# SensorStick_IMUedits_HeaderPins.net
KiCad netlist of a schematic drawn in EAGLE
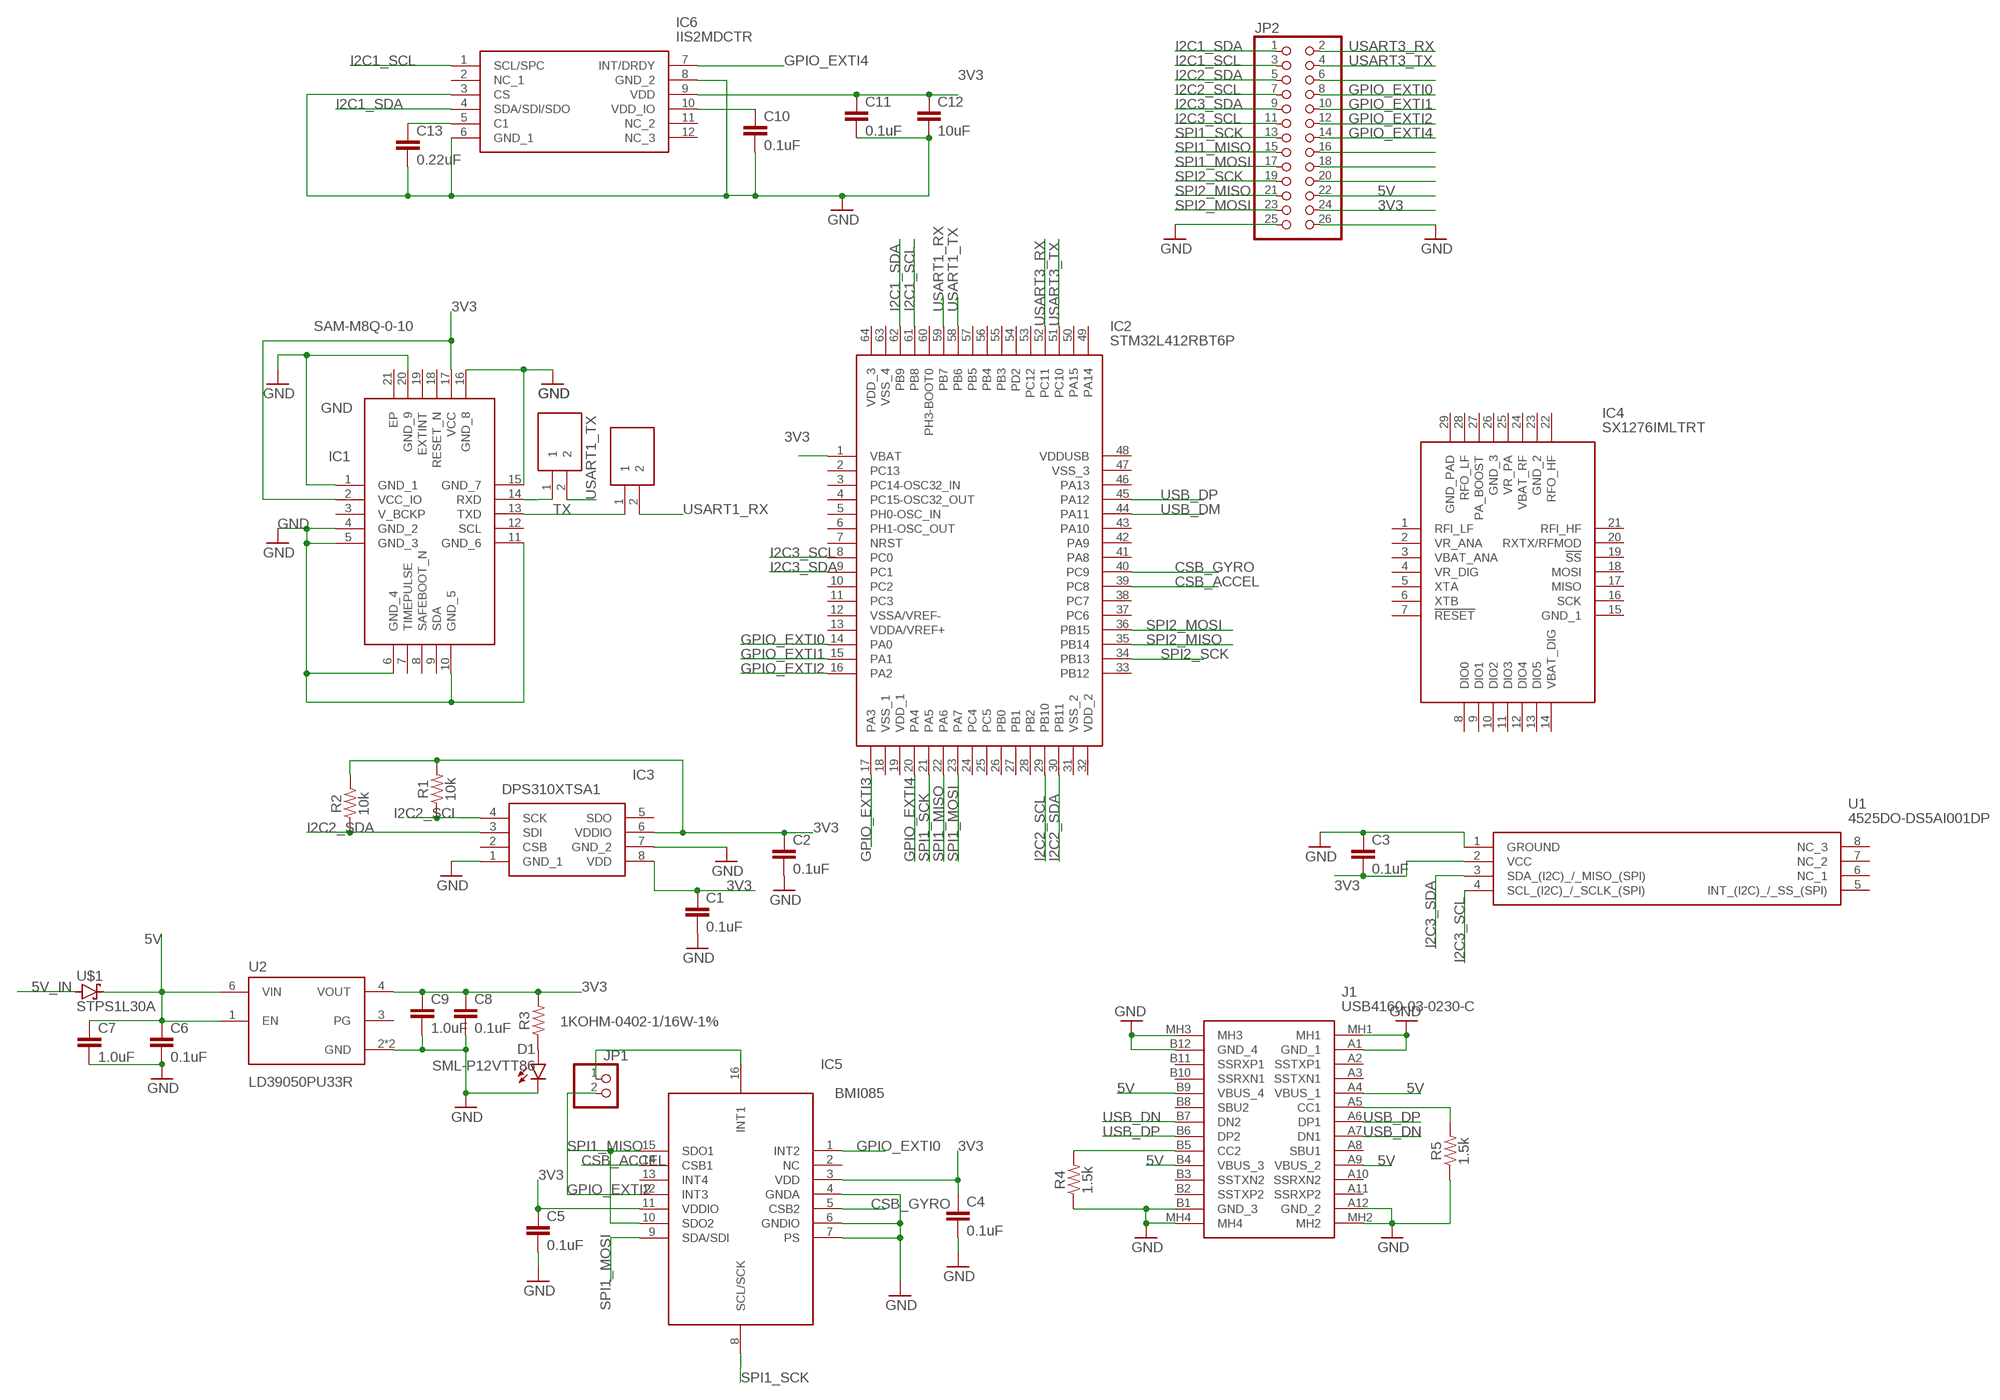
[diagram p0: schematic, sheet 1]

(export (version "E")
  (design (tool "Eeschema 10.0.6"))
  (components
    (comp (ref "C1")
      (value "0.1uF")
      (footprint "eagle-import:0402")
      (libsource (lib "eagle-import") (part "0.1UF-0402-6.3V-10%-X7R"))
    )
    (comp (ref "C2")
      (value "0.1uF")
      (footprint "eagle-import:0402")
      (libsource (lib "eagle-import") (part "0.1UF-0402-6.3V-10%-X7R"))
    )
    (comp (ref "C3")
      (value "0.1uF")
      (footprint "eagle-import:0402")
      (libsource (lib "eagle-import") (part "0.1UF-0402-6.3V-10%-X7R"))
    )
    (comp (ref "C4")
      (value "0.1uF")
      (footprint "eagle-import:0402")
      (libsource (lib "eagle-import") (part "0.1UF-0402-6.3V-10%-X7R"))
    )
    (comp (ref "C5")
      (value "0.1uF")
      (footprint "eagle-import:0402")
      (libsource (lib "eagle-import") (part "0.1UF-0402-6.3V-10%-X7R"))
    )
    (comp (ref "C6")
      (value "0.1uF")
      (footprint "eagle-import:0402")
      (libsource (lib "eagle-import") (part "0.1UF-0402-6.3V-10%-X7R"))
    )
    (comp (ref "C7")
      (value "1.0uF")
      (footprint "eagle-import:0402")
      (libsource (lib "eagle-import") (part "1.0UF-0402-16V-10%"))
    )
    (comp (ref "C8")
      (value "0.1uF")
      (footprint "eagle-import:0402")
      (libsource (lib "eagle-import") (part "0.1UF-0402-6.3V-10%-X7R"))
    )
    (comp (ref "C9")
      (value "1.0uF")
      (footprint "eagle-import:0402")
      (libsource (lib "eagle-import") (part "1.0UF-0402-16V-10%"))
    )
    (comp (ref "C10")
      (value "0.1uF")
      (footprint "eagle-import:0402")
      (libsource (lib "eagle-import") (part "0.1UF-0402-6.3V-10%-X7R"))
    )
    (comp (ref "C11")
      (value "0.1uF")
      (footprint "eagle-import:0402")
      (libsource (lib "eagle-import") (part "0.1UF-0402-6.3V-10%-X7R"))
    )
    (comp (ref "C12")
      (value "10uF")
      (footprint "eagle-import:0603")
      (libsource (lib "eagle-import") (part "10UF-0603-6.3V-20%"))
    )
    (comp (ref "C13")
      (value "0.22uF")
      (footprint "eagle-import:0603")
      (libsource (lib "eagle-import") (part "0.22UF-0603-25V-10%"))
    )
    (comp (ref "D1")
      (value "SML-P12VTT86")
      (footprint "eagle-import:LED_SML-P11UTT86R")
      (fields (field (name "MF") "Rohm"))
      (libsource (lib "eagle-import") (part "SML-P12VTT86"))
    )
    (comp (ref "FB1")
      (value "BLM15HD102SN1")
      (footprint "eagle-import:NFZ15SG152SN10B")
      (libsource (lib "eagle-import") (part "BLM15HD102SN1"))
    )
    (comp (ref "FB2")
      (value "BLM15HD102SN1")
      (footprint "eagle-import:NFZ15SG152SN10B")
      (libsource (lib "eagle-import") (part "BLM15HD102SN1"))
    )
    (comp (ref "IC1")
      (value "SAM-M8Q-0-10")
      (footprint "eagle-import:SAMM8Q010")
      (libsource (lib "eagle-import") (part "SAM-M8Q-0-10"))
    )
    (comp (ref "IC2")
      (value "STM32L412RBT6P")
      (footprint "eagle-import:QFP50P1200X1200X160-64N")
      (fields (field (name "MOUSER_PART_NUMBER") "511-STM32L412RBT6P"))
      (libsource (lib "eagle-import") (part "STM32L412RBT6P"))
    )
    (comp (ref "IC3")
      (value "DPS310XTSA1")
      (footprint "eagle-import:DPS310XTSA1")
      (fields (field (name "MOUSER_PART_NUMBER") "726-DPS310XTSA1"))
      (libsource (lib "eagle-import") (part "DPS310XTSA1"))
    )
    (comp (ref "IC4")
      (value "SX1276IMLTRT")
      (footprint "eagle-import:QFN65P600X600X100-29N")
      (fields (field (name "MOUSER_PART_NUMBER") "947-SX1276IMLTRT"))
      (libsource (lib "eagle-import") (part "SX1276IMLTRT"))
    )
    (comp (ref "IC5")
      (value "BMI085")
      (footprint "eagle-import:BMI085")
      (fields (field (name "MOUSER_PART_NUMBER") "262-BMI085"))
      (libsource (lib "eagle-import") (part "BMI085"))
    )
    (comp (ref "IC6")
      (value "IIS2MDCTR")
      (footprint "eagle-import:IIS2MDCTR")
      (fields (field (name "MOUSER_PART_NUMBER") "511-IIS2MDCTR"))
      (libsource (lib "eagle-import") (part "IIS2MDCTR"))
    )
    (comp (ref "J1")
      (value "USB4160-03-0230-C")
      (footprint "eagle-import:USB4160030230C")
      (fields (field (name "MOUSER_PART_NUMBER") "640-USB4160-3-0230-C"))
      (libsource (lib "eagle-import") (part "USB4160-03-0230-C"))
    )
    (comp (ref "JP1")
      (value "PINHD-1X2")
      (footprint "eagle-import:1X02")
      (libsource (lib "eagle-import") (part "PINHD-1X2"))
    )
    (comp (ref "JP2")
      (value "PINHD-2X13")
      (footprint "eagle-import:2X13")
      (libsource (lib "eagle-import") (part "PINHD-2X13"))
    )
    (comp (ref "R1")
      (value "10k")
      (footprint "eagle-import:0402")
      (libsource (lib "eagle-import") (part "10KOHM-0402-1/16W-1%"))
    )
    (comp (ref "R2")
      (value "10k")
      (footprint "eagle-import:0402")
      (libsource (lib "eagle-import") (part "10KOHM-0402-1/16W-1%"))
    )
    (comp (ref "R3")
      (value "1KOHM-0402-1/16W-1%")
      (footprint "eagle-import:0402")
      (libsource (lib "eagle-import") (part "1KOHM-0402-1/16W-1%"))
    )
    (comp (ref "R4")
      (value "1.5k")
      (footprint "eagle-import:0603")
      (libsource (lib "eagle-import") (part "1.5KOHM-0603-1/10W-1%"))
    )
    (comp (ref "R5")
      (value "1.5k")
      (footprint "eagle-import:0603")
      (libsource (lib "eagle-import") (part "1.5KOHM-0603-1/10W-1%"))
    )
    (comp (ref "U$1")
      (value "STPS1L30A")
      (footprint "eagle-import:DIOM5226X223N")
      (libsource (lib "eagle-import") (part "STPS1L30A"))
    )
    (comp (ref "U1")
      (value "4525DO-DS5AI001DP")
      (footprint "eagle-import:4525DO-DS...P")
      (fields (field (name "MOUSER_PART_NUMBER") "824-4525DODS5AI001DP"))
      (libsource (lib "eagle-import") (part "4525DO-DS5AI001DP"))
    )
    (comp (ref "U2")
      (value "LD39050PU33R")
      (footprint "eagle-import:SON95P300X300X100-7N")
      (fields (field (name "MF") "STMicroelectronics"))
      (libsource (lib "eagle-import") (part "LD39050PU33R"))
    )
  )
  (nets
    (net (code "1") (name "/3V3") (class "Default")
      (node (ref "C1") (pin "1") (pinfunction "1_1") (pintype "passive"))
      (node (ref "C11") (pin "1") (pinfunction "1_1") (pintype "passive"))
      (node (ref "C12") (pin "1") (pinfunction "1_1") (pintype "passive"))
      (node (ref "C2") (pin "1") (pinfunction "1_1") (pintype "passive"))
      (node (ref "C3") (pin "2") (pinfunction "2_2") (pintype "passive"))
      (node (ref "C4") (pin "1") (pinfunction "1_1") (pintype "passive"))
      (node (ref "C5") (pin "1") (pinfunction "1_1") (pintype "passive"))
      (node (ref "C8") (pin "1") (pinfunction "1_1") (pintype "passive"))
      (node (ref "C9") (pin "1") (pinfunction "1_1") (pintype "passive"))
      (node (ref "IC1") (pin "17") (pinfunction "VCC_17") (pintype "bidirectional"))
      (node (ref "IC1") (pin "2") (pinfunction "VCC_IO_2") (pintype "bidirectional"))
      (node (ref "IC2") (pin "1") (pinfunction "VBAT_1") (pintype "bidirectional"))
      (node (ref "IC3") (pin "6") (pinfunction "VDDIO_6") (pintype "bidirectional"))
      (node (ref "IC3") (pin "8") (pinfunction "VDD_8") (pintype "bidirectional"))
      (node (ref "IC5") (pin "11") (pinfunction "VDDIO_11") (pintype "bidirectional"))
      (node (ref "IC5") (pin "3") (pinfunction "VDD_3") (pintype "bidirectional"))
      (node (ref "IC6") (pin "9") (pinfunction "VDD_9") (pintype "bidirectional"))
      (node (ref "JP2") (pin "24") (pinfunction "24_24") (pintype "passive"))
      (node (ref "R1") (pin "2") (pinfunction "2_2") (pintype "passive"))
      (node (ref "R2") (pin "2") (pinfunction "2_2") (pintype "passive"))
      (node (ref "R3") (pin "2") (pinfunction "2_2") (pintype "passive"))
      (node (ref "U1") (pin "2") (pinfunction "VCC_2") (pintype "power_in"))
      (node (ref "U2") (pin "4") (pinfunction "VOUT_4") (pintype "output"))
    )
    (net (code "2") (name "/5V") (class "Default")
      (node (ref "C6") (pin "1") (pinfunction "1_1") (pintype "passive"))
      (node (ref "C7") (pin "1") (pinfunction "1_1") (pintype "passive"))
      (node (ref "J1") (pin "A4") (pinfunction "VBUS_1_A4") (pintype "bidirectional"))
      (node (ref "J1") (pin "A9") (pinfunction "VBUS_2_A9") (pintype "bidirectional"))
      (node (ref "J1") (pin "B4") (pinfunction "VBUS_3_B4") (pintype "bidirectional"))
      (node (ref "J1") (pin "B9") (pinfunction "VBUS_4_B9") (pintype "bidirectional"))
      (node (ref "JP2") (pin "22") (pinfunction "22_22") (pintype "passive"))
      (node (ref "U$1") (pin "1") (pinfunction "C_1") (pintype "passive"))
      (node (ref "U2") (pin "1") (pinfunction "EN_1") (pintype "input"))
      (node (ref "U2") (pin "6") (pinfunction "VIN_6") (pintype "power_in"))
    )
    (net (code "3") (name "/5V_IN") (class "Default")
      (node (ref "U$1") (pin "2") (pinfunction "A_2") (pintype "passive"))
    )
    (net (code "4") (name "/CSB_ACCEL") (class "Default")
      (node (ref "IC2") (pin "39") (pinfunction "PC8_39") (pintype "bidirectional"))
      (node (ref "IC5") (pin "14") (pinfunction "CSB1_14") (pintype "bidirectional"))
    )
    (net (code "5") (name "/CSB_GYRO") (class "Default")
      (node (ref "IC2") (pin "40") (pinfunction "PC9_40") (pintype "bidirectional"))
      (node (ref "IC5") (pin "5") (pinfunction "CSB2_5") (pintype "bidirectional"))
    )
    (net (code "6") (name "/GPIO_EXTI0") (class "Default")
      (node (ref "IC2") (pin "14") (pinfunction "PA0_14") (pintype "bidirectional"))
      (node (ref "IC5") (pin "1") (pinfunction "INT2_1") (pintype "bidirectional"))
      (node (ref "JP2") (pin "8") (pinfunction "8_8") (pintype "passive"))
    )
    (net (code "7") (name "/GPIO_EXTI1") (class "Default")
      (node (ref "IC2") (pin "15") (pinfunction "PA1_15") (pintype "bidirectional"))
      (node (ref "JP2") (pin "10") (pinfunction "10_10") (pintype "passive"))
    )
    (net (code "8") (name "/GPIO_EXTI2") (class "Default")
      (node (ref "IC2") (pin "16") (pinfunction "PA2_16") (pintype "bidirectional"))
      (node (ref "IC5") (pin "12") (pinfunction "INT3_12") (pintype "bidirectional"))
      (node (ref "JP1") (pin "2") (pinfunction "2_2") (pintype "passive"))
      (node (ref "JP2") (pin "12") (pinfunction "12_12") (pintype "passive"))
    )
    (net (code "9") (name "/GPIO_EXTI3") (class "Default")
      (node (ref "IC2") (pin "17") (pinfunction "PA3_17") (pintype "bidirectional"))
    )
    (net (code "10") (name "/GPIO_EXTI4") (class "Default")
      (node (ref "IC2") (pin "20") (pinfunction "PA4_20") (pintype "bidirectional"))
      (node (ref "IC6") (pin "7") (pinfunction "INT/DRDY_7") (pintype "bidirectional"))
      (node (ref "JP2") (pin "14") (pinfunction "14_14") (pintype "passive"))
    )
    (net (code "11") (name "/I2C1_SCL") (class "Default")
      (node (ref "IC2") (pin "61") (pinfunction "PB8_61") (pintype "bidirectional"))
      (node (ref "IC6") (pin "1") (pinfunction "SCL/SPC_1") (pintype "bidirectional"))
      (node (ref "JP2") (pin "3") (pinfunction "3_3") (pintype "passive"))
    )
    (net (code "12") (name "/I2C1_SDA") (class "Default")
      (node (ref "IC2") (pin "62") (pinfunction "PB9_62") (pintype "bidirectional"))
      (node (ref "IC6") (pin "4") (pinfunction "SDA/SDI/SDO_4") (pintype "bidirectional"))
      (node (ref "JP2") (pin "1") (pinfunction "1_1") (pintype "passive"))
    )
    (net (code "13") (name "/I2C2_SCL") (class "Default")
      (node (ref "IC2") (pin "29") (pinfunction "PB10_29") (pintype "bidirectional"))
      (node (ref "IC3") (pin "4") (pinfunction "SCK_4") (pintype "bidirectional"))
      (node (ref "JP2") (pin "7") (pinfunction "7_7") (pintype "passive"))
      (node (ref "R1") (pin "1") (pinfunction "1_1") (pintype "passive"))
    )
    (net (code "14") (name "/I2C2_SDA") (class "Default")
      (node (ref "IC2") (pin "30") (pinfunction "PB11_30") (pintype "bidirectional"))
      (node (ref "IC3") (pin "3") (pinfunction "SDI_3") (pintype "bidirectional"))
      (node (ref "JP2") (pin "5") (pinfunction "5_5") (pintype "passive"))
      (node (ref "R2") (pin "1") (pinfunction "1_1") (pintype "passive"))
    )
    (net (code "15") (name "/I2C3_SCL") (class "Default")
      (node (ref "IC2") (pin "8") (pinfunction "PC0_8") (pintype "bidirectional"))
      (node (ref "JP2") (pin "11") (pinfunction "11_11") (pintype "passive"))
      (node (ref "U1") (pin "4") (pinfunction "SCL_(I2C)_/_SCLK_(SPI)_4") (pintype "bidirectional"))
    )
    (net (code "16") (name "/I2C3_SDA") (class "Default")
      (node (ref "IC2") (pin "9") (pinfunction "PC1_9") (pintype "bidirectional"))
      (node (ref "JP2") (pin "9") (pinfunction "9_9") (pintype "passive"))
      (node (ref "U1") (pin "3") (pinfunction "SDA_(I2C)_/_MISO_(SPI)_3") (pintype "bidirectional"))
    )
    (net (code "17") (name "/SPI1_MISO") (class "Default")
      (node (ref "IC2") (pin "22") (pinfunction "PA6_22") (pintype "bidirectional"))
      (node (ref "IC5") (pin "10") (pinfunction "SDO2_10") (pintype "bidirectional"))
      (node (ref "IC5") (pin "15") (pinfunction "SDO1_15") (pintype "bidirectional"))
      (node (ref "JP2") (pin "15") (pinfunction "15_15") (pintype "passive"))
    )
    (net (code "18") (name "/SPI1_MOSI") (class "Default")
      (node (ref "IC2") (pin "23") (pinfunction "PA7_23") (pintype "bidirectional"))
      (node (ref "IC5") (pin "9") (pinfunction "SDA/SDI_9") (pintype "bidirectional"))
      (node (ref "JP2") (pin "17") (pinfunction "17_17") (pintype "passive"))
    )
    (net (code "19") (name "/SPI1_SCK") (class "Default")
      (node (ref "IC2") (pin "21") (pinfunction "PA5_21") (pintype "bidirectional"))
      (node (ref "IC5") (pin "8") (pinfunction "SCL/SCK_8") (pintype "bidirectional"))
      (node (ref "JP2") (pin "13") (pinfunction "13_13") (pintype "passive"))
    )
    (net (code "20") (name "/SPI2_MISO") (class "Default")
      (node (ref "IC2") (pin "35") (pinfunction "PB14_35") (pintype "bidirectional"))
      (node (ref "JP2") (pin "21") (pinfunction "21_21") (pintype "passive"))
    )
    (net (code "21") (name "/SPI2_MOSI") (class "Default")
      (node (ref "IC2") (pin "36") (pinfunction "PB15_36") (pintype "bidirectional"))
      (node (ref "JP2") (pin "23") (pinfunction "23_23") (pintype "passive"))
    )
    (net (code "22") (name "/SPI2_SCK") (class "Default")
      (node (ref "IC2") (pin "34") (pinfunction "PB13_34") (pintype "bidirectional"))
      (node (ref "JP2") (pin "19") (pinfunction "19_19") (pintype "passive"))
    )
    (net (code "23") (name "/TX") (class "Default")
      (node (ref "FB1") (pin "1") (pinfunction "1_1") (pintype "bidirectional"))
      (node (ref "IC1") (pin "13") (pinfunction "TXD_13") (pintype "bidirectional"))
    )
    (net (code "24") (name "/USART1_RX") (class "Default")
      (node (ref "FB1") (pin "2") (pinfunction "2_2") (pintype "bidirectional"))
      (node (ref "IC2") (pin "59") (pinfunction "PB7_59") (pintype "bidirectional"))
    )
    (net (code "25") (name "/USART1_TX") (class "Default")
      (node (ref "FB2") (pin "2") (pinfunction "2_2") (pintype "bidirectional"))
      (node (ref "IC2") (pin "58") (pinfunction "PB6_58") (pintype "bidirectional"))
    )
    (net (code "26") (name "/USART3_RX") (class "Default")
      (node (ref "IC2") (pin "52") (pinfunction "PC11_52") (pintype "bidirectional"))
      (node (ref "JP2") (pin "2") (pinfunction "2_2") (pintype "passive"))
    )
    (net (code "27") (name "/USART3_TX") (class "Default")
      (node (ref "IC2") (pin "51") (pinfunction "PC10_51") (pintype "bidirectional"))
      (node (ref "JP2") (pin "4") (pinfunction "4_4") (pintype "passive"))
    )
    (net (code "28") (name "/USB_DM") (class "Default")
      (node (ref "IC2") (pin "44") (pinfunction "PA11_44") (pintype "bidirectional"))
    )
    (net (code "29") (name "/USB_DN") (class "Default")
      (node (ref "J1") (pin "A7") (pinfunction "DN1_A7") (pintype "bidirectional"))
      (node (ref "J1") (pin "B7") (pinfunction "DN2_B7") (pintype "bidirectional"))
    )
    (net (code "30") (name "/USB_DP") (class "Default")
      (node (ref "IC2") (pin "45") (pinfunction "PA12_45") (pintype "bidirectional"))
      (node (ref "J1") (pin "A6") (pinfunction "DP1_A6") (pintype "bidirectional"))
      (node (ref "J1") (pin "B6") (pinfunction "DP2_B6") (pintype "bidirectional"))
    )
    (net (code "31") (name "GND") (class "Default")
      (node (ref "C1") (pin "2") (pinfunction "2_2") (pintype "passive"))
      (node (ref "C10") (pin "2") (pinfunction "2_2") (pintype "passive"))
      (node (ref "C11") (pin "2") (pinfunction "2_2") (pintype "passive"))
      (node (ref "C12") (pin "2") (pinfunction "2_2") (pintype "passive"))
      (node (ref "C13") (pin "2") (pinfunction "2_2") (pintype "passive"))
      (node (ref "C2") (pin "2") (pinfunction "2_2") (pintype "passive"))
      (node (ref "C3") (pin "1") (pinfunction "1_1") (pintype "passive"))
      (node (ref "C4") (pin "2") (pinfunction "2_2") (pintype "passive"))
      (node (ref "C5") (pin "2") (pinfunction "2_2") (pintype "passive"))
      (node (ref "C6") (pin "2") (pinfunction "2_2") (pintype "passive"))
      (node (ref "C7") (pin "2") (pinfunction "2_2") (pintype "passive"))
      (node (ref "C8") (pin "2") (pinfunction "2_2") (pintype "passive"))
      (node (ref "C9") (pin "2") (pinfunction "2_2") (pintype "passive"))
      (node (ref "D1") (pin "C") (pinfunction "C_C") (pintype "passive"))
      (node (ref "IC1") (pin "1") (pinfunction "GND_1_1") (pintype "bidirectional"))
      (node (ref "IC1") (pin "10") (pinfunction "GND_5_10") (pintype "bidirectional"))
      (node (ref "IC1") (pin "11") (pinfunction "GND_6_11") (pintype "bidirectional"))
      (node (ref "IC1") (pin "15") (pinfunction "GND_7_15") (pintype "bidirectional"))
      (node (ref "IC1") (pin "16") (pinfunction "GND_8_16") (pintype "bidirectional"))
      (node (ref "IC1") (pin "20") (pinfunction "GND_9_20") (pintype "bidirectional"))
      (node (ref "IC1") (pin "4") (pinfunction "GND_2_4") (pintype "bidirectional"))
      (node (ref "IC1") (pin "5") (pinfunction "GND_3_5") (pintype "bidirectional"))
      (node (ref "IC1") (pin "6") (pinfunction "GND_4_6") (pintype "bidirectional"))
      (node (ref "IC3") (pin "1") (pinfunction "GND_1_1") (pintype "bidirectional"))
      (node (ref "IC3") (pin "7") (pinfunction "GND_2_7") (pintype "bidirectional"))
      (node (ref "IC5") (pin "4") (pinfunction "GNDA_4") (pintype "bidirectional"))
      (node (ref "IC5") (pin "6") (pinfunction "GNDIO_6") (pintype "bidirectional"))
      (node (ref "IC5") (pin "7") (pinfunction "PS_7") (pintype "bidirectional"))
      (node (ref "IC6") (pin "3") (pinfunction "CS_3") (pintype "bidirectional"))
      (node (ref "IC6") (pin "6") (pinfunction "GND_1_6") (pintype "bidirectional"))
      (node (ref "IC6") (pin "8") (pinfunction "GND_2_8") (pintype "bidirectional"))
      (node (ref "J1") (pin "A1") (pinfunction "GND_1_A1") (pintype "bidirectional"))
      (node (ref "J1") (pin "A12") (pinfunction "GND_2_A12") (pintype "bidirectional"))
      (node (ref "J1") (pin "B1") (pinfunction "GND_3_B1") (pintype "bidirectional"))
      (node (ref "J1") (pin "B12") (pinfunction "GND_4_B12") (pintype "bidirectional"))
      (node (ref "J1") (pin "MH1") (pinfunction "MH1_MH1") (pintype "bidirectional"))
      (node (ref "J1") (pin "MH2") (pinfunction "MH2_MH2") (pintype "bidirectional"))
      (node (ref "J1") (pin "MH3") (pinfunction "MH3_MH3") (pintype "bidirectional"))
      (node (ref "J1") (pin "MH4") (pinfunction "MH4_MH4") (pintype "bidirectional"))
      (node (ref "JP2") (pin "25") (pinfunction "25_25") (pintype "passive"))
      (node (ref "JP2") (pin "26") (pinfunction "26_26") (pintype "passive"))
      (node (ref "R4") (pin "1") (pinfunction "1_1") (pintype "passive"))
      (node (ref "R5") (pin "1") (pinfunction "1_1") (pintype "passive"))
      (node (ref "U1") (pin "1") (pinfunction "GROUND_1") (pintype "power_in"))
      (node (ref "U2") (pin "2") (pinfunction "GND_2") (pintype "power_in"))
      (node (ref "U2") (pin "7") (pinfunction "GND_7") (pintype "power_in"))
    )
    (net (code "32") (name "Net-(D1-PadA)") (class "Default")
      (node (ref "D1") (pin "A") (pinfunction "A_A") (pintype "passive"))
      (node (ref "R3") (pin "1") (pinfunction "1_1") (pintype "passive"))
    )
    (net (code "33") (name "Net-(IC1-RXD)") (class "Default")
      (node (ref "FB2") (pin "1") (pinfunction "1_1") (pintype "bidirectional"))
      (node (ref "IC1") (pin "14") (pinfunction "RXD_14") (pintype "bidirectional"))
    )
    (net (code "34") (name "Net-(IC5-INT1)") (class "Default")
      (node (ref "IC5") (pin "16") (pinfunction "INT1_16") (pintype "bidirectional"))
      (node (ref "JP1") (pin "1") (pinfunction "1_1") (pintype "passive"))
    )
    (net (code "35") (name "Net-(IC6-C1)") (class "Default")
      (node (ref "C13") (pin "1") (pinfunction "1_1") (pintype "passive"))
      (node (ref "IC6") (pin "5") (pinfunction "C1_5") (pintype "bidirectional"))
    )
    (net (code "36") (name "Net-(IC6-VDD_IO)") (class "Default")
      (node (ref "C10") (pin "1") (pinfunction "1_1") (pintype "passive"))
      (node (ref "IC6") (pin "10") (pinfunction "VDD_IO_10") (pintype "bidirectional"))
    )
    (net (code "37") (name "Net-(J1-CC1)") (class "Default")
      (node (ref "J1") (pin "A5") (pinfunction "CC1_A5") (pintype "bidirectional"))
      (node (ref "R5") (pin "2") (pinfunction "2_2") (pintype "passive"))
    )
    (net (code "38") (name "Net-(J1-CC2)") (class "Default")
      (node (ref "J1") (pin "B5") (pinfunction "CC2_B5") (pintype "bidirectional"))
      (node (ref "R4") (pin "2") (pinfunction "2_2") (pintype "passive"))
    )
    (net (code "39") (name "unconnected-(IC1-EP-Pad21)") (class "Default")
      (node (ref "IC1") (pin "21") (pinfunction "EP_21") (pintype "bidirectional"))
    )
    (net (code "40") (name "unconnected-(IC1-EXTINT-Pad19)") (class "Default")
      (node (ref "IC1") (pin "19") (pinfunction "EXTINT_19") (pintype "bidirectional"))
    )
    (net (code "41") (name "unconnected-(IC1-RESET_N-Pad18)") (class "Default")
      (node (ref "IC1") (pin "18") (pinfunction "RESET_N_18") (pintype "bidirectional"))
    )
    (net (code "42") (name "unconnected-(IC1-SAFEBOOT_N-Pad8)") (class "Default")
      (node (ref "IC1") (pin "8") (pinfunction "SAFEBOOT_N_8") (pintype "bidirectional"))
    )
    (net (code "43") (name "unconnected-(IC1-SCL-Pad12)") (class "Default")
      (node (ref "IC1") (pin "12") (pinfunction "SCL_12") (pintype "bidirectional"))
    )
    (net (code "44") (name "unconnected-(IC1-SDA-Pad9)") (class "Default")
      (node (ref "IC1") (pin "9") (pinfunction "SDA_9") (pintype "bidirectional"))
    )
    (net (code "45") (name "unconnected-(IC1-TIMEPULSE-Pad7)") (class "Default")
      (node (ref "IC1") (pin "7") (pinfunction "TIMEPULSE_7") (pintype "bidirectional"))
    )
    (net (code "46") (name "unconnected-(IC1-V_BCKP-Pad3)") (class "Default")
      (node (ref "IC1") (pin "3") (pinfunction "V_BCKP_3") (pintype "bidirectional"))
    )
    (net (code "47") (name "unconnected-(IC2-NRST-Pad7)") (class "Default")
      (node (ref "IC2") (pin "7") (pinfunction "NRST_7") (pintype "bidirectional"))
    )
    (net (code "48") (name "unconnected-(IC2-PA8-Pad41)") (class "Default")
      (node (ref "IC2") (pin "41") (pinfunction "PA8_41") (pintype "bidirectional"))
    )
    (net (code "49") (name "unconnected-(IC2-PA9-Pad42)") (class "Default")
      (node (ref "IC2") (pin "42") (pinfunction "PA9_42") (pintype "bidirectional"))
    )
    (net (code "50") (name "unconnected-(IC2-PA10-Pad43)") (class "Default")
      (node (ref "IC2") (pin "43") (pinfunction "PA10_43") (pintype "bidirectional"))
    )
    (net (code "51") (name "unconnected-(IC2-PA13-Pad46)") (class "Default")
      (node (ref "IC2") (pin "46") (pinfunction "PA13_46") (pintype "bidirectional"))
    )
    (net (code "52") (name "unconnected-(IC2-PA14-Pad49)") (class "Default")
      (node (ref "IC2") (pin "49") (pinfunction "PA14_49") (pintype "bidirectional"))
    )
    (net (code "53") (name "unconnected-(IC2-PA15-Pad50)") (class "Default")
      (node (ref "IC2") (pin "50") (pinfunction "PA15_50") (pintype "bidirectional"))
    )
    (net (code "54") (name "unconnected-(IC2-PB0-Pad26)") (class "Default")
      (node (ref "IC2") (pin "26") (pinfunction "PB0_26") (pintype "bidirectional"))
    )
    (net (code "55") (name "unconnected-(IC2-PB1-Pad27)") (class "Default")
      (node (ref "IC2") (pin "27") (pinfunction "PB1_27") (pintype "bidirectional"))
    )
    (net (code "56") (name "unconnected-(IC2-PB2-Pad28)") (class "Default")
      (node (ref "IC2") (pin "28") (pinfunction "PB2_28") (pintype "bidirectional"))
    )
    (net (code "57") (name "unconnected-(IC2-PB3-Pad55)") (class "Default")
      (node (ref "IC2") (pin "55") (pinfunction "PB3_55") (pintype "bidirectional"))
    )
    (net (code "58") (name "unconnected-(IC2-PB4-Pad56)") (class "Default")
      (node (ref "IC2") (pin "56") (pinfunction "PB4_56") (pintype "bidirectional"))
    )
    (net (code "59") (name "unconnected-(IC2-PB5-Pad57)") (class "Default")
      (node (ref "IC2") (pin "57") (pinfunction "PB5_57") (pintype "bidirectional"))
    )
    (net (code "60") (name "unconnected-(IC2-PB12-Pad33)") (class "Default")
      (node (ref "IC2") (pin "33") (pinfunction "PB12_33") (pintype "bidirectional"))
    )
    (net (code "61") (name "unconnected-(IC2-PC2-Pad10)") (class "Default")
      (node (ref "IC2") (pin "10") (pinfunction "PC2_10") (pintype "bidirectional"))
    )
    (net (code "62") (name "unconnected-(IC2-PC3-Pad11)") (class "Default")
      (node (ref "IC2") (pin "11") (pinfunction "PC3_11") (pintype "bidirectional"))
    )
    (net (code "63") (name "unconnected-(IC2-PC4-Pad24)") (class "Default")
      (node (ref "IC2") (pin "24") (pinfunction "PC4_24") (pintype "bidirectional"))
    )
    (net (code "64") (name "unconnected-(IC2-PC5-Pad25)") (class "Default")
      (node (ref "IC2") (pin "25") (pinfunction "PC5_25") (pintype "bidirectional"))
    )
    (net (code "65") (name "unconnected-(IC2-PC6-Pad37)") (class "Default")
      (node (ref "IC2") (pin "37") (pinfunction "PC6_37") (pintype "bidirectional"))
    )
    (net (code "66") (name "unconnected-(IC2-PC7-Pad38)") (class "Default")
      (node (ref "IC2") (pin "38") (pinfunction "PC7_38") (pintype "bidirectional"))
    )
    (net (code "67") (name "unconnected-(IC2-PC12-Pad53)") (class "Default")
      (node (ref "IC2") (pin "53") (pinfunction "PC12_53") (pintype "bidirectional"))
    )
    (net (code "68") (name "unconnected-(IC2-PC13-Pad2)") (class "Default")
      (node (ref "IC2") (pin "2") (pinfunction "PC13_2") (pintype "bidirectional"))
    )
    (net (code "69") (name "unconnected-(IC2-PC14-OSC32_IN-Pad3)") (class "Default")
      (node (ref "IC2") (pin "3") (pinfunction "PC14-OSC32_IN_3") (pintype "bidirectional"))
    )
    (net (code "70") (name "unconnected-(IC2-PC15-OSC32_OUT-Pad4)") (class "Default")
      (node (ref "IC2") (pin "4") (pinfunction "PC15-OSC32_OUT_4") (pintype "bidirectional"))
    )
    (net (code "71") (name "unconnected-(IC2-PD2-Pad54)") (class "Default")
      (node (ref "IC2") (pin "54") (pinfunction "PD2_54") (pintype "bidirectional"))
    )
    (net (code "72") (name "unconnected-(IC2-PH0-OSC_IN-Pad5)") (class "Default")
      (node (ref "IC2") (pin "5") (pinfunction "PH0-OSC_IN_5") (pintype "bidirectional"))
    )
    (net (code "73") (name "unconnected-(IC2-PH1-OSC_OUT-Pad6)") (class "Default")
      (node (ref "IC2") (pin "6") (pinfunction "PH1-OSC_OUT_6") (pintype "bidirectional"))
    )
    (net (code "74") (name "unconnected-(IC2-PH3-BOOT0-Pad60)") (class "Default")
      (node (ref "IC2") (pin "60") (pinfunction "PH3-BOOT0_60") (pintype "bidirectional"))
    )
    (net (code "75") (name "unconnected-(IC2-VDDA{slash}VREF+-Pad13)") (class "Default")
      (node (ref "IC2") (pin "13") (pinfunction "VDDA/VREF+_13") (pintype "bidirectional"))
    )
    (net (code "76") (name "unconnected-(IC2-VDDUSB-Pad48)") (class "Default")
      (node (ref "IC2") (pin "48") (pinfunction "VDDUSB_48") (pintype "bidirectional"))
    )
    (net (code "77") (name "unconnected-(IC2-VDD_1-Pad19)") (class "Default")
      (node (ref "IC2") (pin "19") (pinfunction "VDD_1_19") (pintype "bidirectional"))
    )
    (net (code "78") (name "unconnected-(IC2-VDD_2-Pad32)") (class "Default")
      (node (ref "IC2") (pin "32") (pinfunction "VDD_2_32") (pintype "bidirectional"))
    )
    (net (code "79") (name "unconnected-(IC2-VDD_3-Pad64)") (class "Default")
      (node (ref "IC2") (pin "64") (pinfunction "VDD_3_64") (pintype "bidirectional"))
    )
    (net (code "80") (name "unconnected-(IC2-VSSA{slash}VREF--Pad12)") (class "Default")
      (node (ref "IC2") (pin "12") (pinfunction "VSSA/VREF-_12") (pintype "bidirectional"))
    )
    (net (code "81") (name "unconnected-(IC2-VSS_1-Pad18)") (class "Default")
      (node (ref "IC2") (pin "18") (pinfunction "VSS_1_18") (pintype "bidirectional"))
    )
    (net (code "82") (name "unconnected-(IC2-VSS_2-Pad31)") (class "Default")
      (node (ref "IC2") (pin "31") (pinfunction "VSS_2_31") (pintype "bidirectional"))
    )
    (net (code "83") (name "unconnected-(IC2-VSS_3-Pad47)") (class "Default")
      (node (ref "IC2") (pin "47") (pinfunction "VSS_3_47") (pintype "bidirectional"))
    )
    (net (code "84") (name "unconnected-(IC2-VSS_4-Pad63)") (class "Default")
      (node (ref "IC2") (pin "63") (pinfunction "VSS_4_63") (pintype "bidirectional"))
    )
    (net (code "85") (name "unconnected-(IC3-CSB-Pad2)") (class "Default")
      (node (ref "IC3") (pin "2") (pinfunction "CSB_2") (pintype "bidirectional"))
    )
    (net (code "86") (name "unconnected-(IC3-SDO-Pad5)") (class "Default")
      (node (ref "IC3") (pin "5") (pinfunction "SDO_5") (pintype "bidirectional"))
    )
    (net (code "87") (name "unconnected-(IC4-DIO0-Pad8)") (class "Default")
      (node (ref "IC4") (pin "8") (pinfunction "DIO0_8") (pintype "bidirectional"))
    )
    (net (code "88") (name "unconnected-(IC4-DIO1-Pad9)") (class "Default")
      (node (ref "IC4") (pin "9") (pinfunction "DIO1_9") (pintype "bidirectional"))
    )
    (net (code "89") (name "unconnected-(IC4-DIO2-Pad10)") (class "Default")
      (node (ref "IC4") (pin "10") (pinfunction "DIO2_10") (pintype "bidirectional"))
    )
    (net (code "90") (name "unconnected-(IC4-DIO3-Pad11)") (class "Default")
      (node (ref "IC4") (pin "11") (pinfunction "DIO3_11") (pintype "bidirectional"))
    )
    (net (code "91") (name "unconnected-(IC4-DIO4-Pad12)") (class "Default")
      (node (ref "IC4") (pin "12") (pinfunction "DIO4_12") (pintype "bidirectional"))
    )
    (net (code "92") (name "unconnected-(IC4-DIO5-Pad13)") (class "Default")
      (node (ref "IC4") (pin "13") (pinfunction "DIO5_13") (pintype "bidirectional"))
    )
    (net (code "93") (name "unconnected-(IC4-GND_1-Pad15)") (class "Default")
      (node (ref "IC4") (pin "15") (pinfunction "GND_1_15") (pintype "bidirectional"))
    )
    (net (code "94") (name "unconnected-(IC4-GND_2-Pad23)") (class "Default")
      (node (ref "IC4") (pin "23") (pinfunction "GND_2_23") (pintype "bidirectional"))
    )
    (net (code "95") (name "unconnected-(IC4-GND_3-Pad26)") (class "Default")
      (node (ref "IC4") (pin "26") (pinfunction "GND_3_26") (pintype "bidirectional"))
    )
    (net (code "96") (name "unconnected-(IC4-GND_PAD-Pad29)") (class "Default")
      (node (ref "IC4") (pin "29") (pinfunction "GND_PAD_29") (pintype "bidirectional"))
    )
    (net (code "97") (name "unconnected-(IC4-MISO-Pad17)") (class "Default")
      (node (ref "IC4") (pin "17") (pinfunction "MISO_17") (pintype "bidirectional"))
    )
    (net (code "98") (name "unconnected-(IC4-MOSI-Pad18)") (class "Default")
      (node (ref "IC4") (pin "18") (pinfunction "MOSI_18") (pintype "bidirectional"))
    )
    (net (code "99") (name "unconnected-(IC4-PA_BOOST-Pad27)") (class "Default")
      (node (ref "IC4") (pin "27") (pinfunction "PA_BOOST_27") (pintype "bidirectional"))
    )
    (net (code "100") (name "unconnected-(IC4-RFI_HF-Pad21)") (class "Default")
      (node (ref "IC4") (pin "21") (pinfunction "RFI_HF_21") (pintype "bidirectional"))
    )
    (net (code "101") (name "unconnected-(IC4-RFI_LF-Pad1)") (class "Default")
      (node (ref "IC4") (pin "1") (pinfunction "RFI_LF_1") (pintype "bidirectional"))
    )
    (net (code "102") (name "unconnected-(IC4-RFO_HF-Pad22)") (class "Default")
      (node (ref "IC4") (pin "22") (pinfunction "RFO_HF_22") (pintype "bidirectional"))
    )
    (net (code "103") (name "unconnected-(IC4-RFO_LF-Pad28)") (class "Default")
      (node (ref "IC4") (pin "28") (pinfunction "RFO_LF_28") (pintype "bidirectional"))
    )
    (net (code "104") (name "unconnected-(IC4-RXTX{slash}RFMOD-Pad20)") (class "Default")
      (node (ref "IC4") (pin "20") (pinfunction "RXTX/RFMOD_20") (pintype "bidirectional"))
    )
    (net (code "105") (name "unconnected-(IC4-SCK-Pad16)") (class "Default")
      (node (ref "IC4") (pin "16") (pinfunction "SCK_16") (pintype "bidirectional"))
    )
    (net (code "106") (name "unconnected-(IC4-VBAT_ANA-Pad3)") (class "Default")
      (node (ref "IC4") (pin "3") (pinfunction "VBAT_ANA_3") (pintype "bidirectional"))
    )
    (net (code "107") (name "unconnected-(IC4-VBAT_DIG-Pad14)") (class "Default")
      (node (ref "IC4") (pin "14") (pinfunction "VBAT_DIG_14") (pintype "bidirectional"))
    )
    (net (code "108") (name "unconnected-(IC4-VBAT_RF-Pad24)") (class "Default")
      (node (ref "IC4") (pin "24") (pinfunction "VBAT_RF_24") (pintype "bidirectional"))
    )
    (net (code "109") (name "unconnected-(IC4-VR_ANA-Pad2)") (class "Default")
      (node (ref "IC4") (pin "2") (pinfunction "VR_ANA_2") (pintype "bidirectional"))
    )
    (net (code "110") (name "unconnected-(IC4-VR_DIG-Pad4)") (class "Default")
      (node (ref "IC4") (pin "4") (pinfunction "VR_DIG_4") (pintype "bidirectional"))
    )
    (net (code "111") (name "unconnected-(IC4-VR_PA-Pad25)") (class "Default")
      (node (ref "IC4") (pin "25") (pinfunction "VR_PA_25") (pintype "bidirectional"))
    )
    (net (code "112") (name "unconnected-(IC4-XTA-Pad5)") (class "Default")
      (node (ref "IC4") (pin "5") (pinfunction "XTA_5") (pintype "bidirectional"))
    )
    (net (code "113") (name "unconnected-(IC4-XTB-Pad6)") (class "Default")
      (node (ref "IC4") (pin "6") (pinfunction "XTB_6") (pintype "bidirectional"))
    )
    (net (code "114") (name "unconnected-(IC4-~{RESET}-Pad7)") (class "Default")
      (node (ref "IC4") (pin "7") (pinfunction "~{RESET}_7") (pintype "bidirectional"))
    )
    (net (code "115") (name "unconnected-(IC4-~{SS}-Pad19)") (class "Default")
      (node (ref "IC4") (pin "19") (pinfunction "~{SS}_19") (pintype "bidirectional"))
    )
    (net (code "116") (name "unconnected-(IC5-INT4-Pad13)") (class "Default")
      (node (ref "IC5") (pin "13") (pinfunction "INT4_13") (pintype "bidirectional"))
    )
    (net (code "117") (name "unconnected-(IC5-NC-Pad2)") (class "Default")
      (node (ref "IC5") (pin "2") (pinfunction "NC_2") (pintype "no_connect"))
    )
    (net (code "118") (name "unconnected-(IC6-NC_1-Pad2)") (class "Default")
      (node (ref "IC6") (pin "2") (pinfunction "NC_1_2") (pintype "bidirectional"))
    )
    (net (code "119") (name "unconnected-(IC6-NC_2-Pad11)") (class "Default")
      (node (ref "IC6") (pin "11") (pinfunction "NC_2_11") (pintype "bidirectional"))
    )
    (net (code "120") (name "unconnected-(IC6-NC_3-Pad12)") (class "Default")
      (node (ref "IC6") (pin "12") (pinfunction "NC_3_12") (pintype "bidirectional"))
    )
    (net (code "121") (name "unconnected-(J1-SBU1-PadA8)") (class "Default")
      (node (ref "J1") (pin "A8") (pinfunction "SBU1_A8") (pintype "bidirectional"))
    )
    (net (code "122") (name "unconnected-(J1-SBU2-PadB8)") (class "Default")
      (node (ref "J1") (pin "B8") (pinfunction "SBU2_B8") (pintype "bidirectional"))
    )
    (net (code "123") (name "unconnected-(J1-SSRXN1-PadB10)") (class "Default")
      (node (ref "J1") (pin "B10") (pinfunction "SSRXN1_B10") (pintype "bidirectional"))
    )
    (net (code "124") (name "unconnected-(J1-SSRXN2-PadA10)") (class "Default")
      (node (ref "J1") (pin "A10") (pinfunction "SSRXN2_A10") (pintype "bidirectional"))
    )
    (net (code "125") (name "unconnected-(J1-SSRXP1-PadB11)") (class "Default")
      (node (ref "J1") (pin "B11") (pinfunction "SSRXP1_B11") (pintype "bidirectional"))
    )
    (net (code "126") (name "unconnected-(J1-SSRXP2-PadA11)") (class "Default")
      (node (ref "J1") (pin "A11") (pinfunction "SSRXP2_A11") (pintype "bidirectional"))
    )
    (net (code "127") (name "unconnected-(J1-SSTXN1-PadA3)") (class "Default")
      (node (ref "J1") (pin "A3") (pinfunction "SSTXN1_A3") (pintype "bidirectional"))
    )
    (net (code "128") (name "unconnected-(J1-SSTXN2-PadB3)") (class "Default")
      (node (ref "J1") (pin "B3") (pinfunction "SSTXN2_B3") (pintype "bidirectional"))
    )
    (net (code "129") (name "unconnected-(J1-SSTXP1-PadA2)") (class "Default")
      (node (ref "J1") (pin "A2") (pinfunction "SSTXP1_A2") (pintype "bidirectional"))
    )
    (net (code "130") (name "unconnected-(J1-SSTXP2-PadB2)") (class "Default")
      (node (ref "J1") (pin "B2") (pinfunction "SSTXP2_B2") (pintype "bidirectional"))
    )
    (net (code "131") (name "unconnected-(JP2-Pad6)") (class "Default")
      (node (ref "JP2") (pin "6") (pinfunction "6_6") (pintype "passive"))
    )
    (net (code "132") (name "unconnected-(JP2-Pad16)") (class "Default")
      (node (ref "JP2") (pin "16") (pinfunction "16_16") (pintype "passive"))
    )
    (net (code "133") (name "unconnected-(JP2-Pad18)") (class "Default")
      (node (ref "JP2") (pin "18") (pinfunction "18_18") (pintype "passive"))
    )
    (net (code "134") (name "unconnected-(JP2-Pad20)") (class "Default")
      (node (ref "JP2") (pin "20") (pinfunction "20_20") (pintype "passive"))
    )
    (net (code "135") (name "unconnected-(U1-INT_(I2C)_{slash}_SS_(SPI)-Pad5)") (class "Default")
      (node (ref "U1") (pin "5") (pinfunction "INT_(I2C)_/_SS_(SPI)_5") (pintype "bidirectional"))
    )
    (net (code "136") (name "unconnected-(U1-NC_1-Pad6)") (class "Default")
      (node (ref "U1") (pin "6") (pinfunction "NC_1_6") (pintype "bidirectional"))
    )
    (net (code "137") (name "unconnected-(U1-NC_2-Pad7)") (class "Default")
      (node (ref "U1") (pin "7") (pinfunction "NC_2_7") (pintype "bidirectional"))
    )
    (net (code "138") (name "unconnected-(U1-NC_3-Pad8)") (class "Default")
      (node (ref "U1") (pin "8") (pinfunction "NC_3_8") (pintype "bidirectional"))
    )
    (net (code "139") (name "unconnected-(U2-PG-Pad3)") (class "Default")
      (node (ref "U2") (pin "3") (pinfunction "PG_3") (pintype "bidirectional"))
    )
  )
)
